# ch1.net
KiCad netlist of a schematic drawn in EAGLE
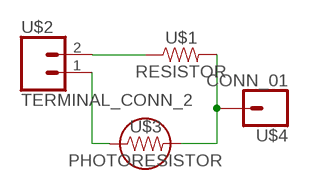
[diagram p0: schematic, sheet 1]

(export (version "E")
  (design (tool "Eeschema 10.0.6"))
  (components
    (comp (ref "U$1")
      (value "RESISTOR")
      (footprint "eagle-import:RESISTOR")
      (libsource (lib "eagle-import") (part "RESISTOR"))
    )
    (comp (ref "U$2")
      (value "TERMINAL_CONN_2")
      (footprint "eagle-import:TERMINAL_CONN_2")
      (libsource (lib "eagle-import") (part "TERMINAL_CONN_2"))
    )
    (comp (ref "U$3")
      (value "PHOTORESISTOR")
      (footprint "eagle-import:PHOTORESISTOR")
      (libsource (lib "eagle-import") (part "PHOTORESISTOR"))
    )
    (comp (ref "U$4")
      (value "CONN_01")
      (footprint "eagle-import:1X01")
      (libsource (lib "eagle-import") (part "CONN_01"))
    )
  )
  (nets
    (net (code "1") (name "Net-(U$1-Pad1)") (class "Default")
      (node (ref "U$1") (pin "1") (pinfunction "1_1") (pintype "passive"))
      (node (ref "U$2") (pin "2") (pinfunction "2_2") (pintype "passive"))
    )
    (net (code "2") (name "Net-(U$3-1)") (class "Default")
      (node (ref "U$2") (pin "1") (pinfunction "1_1") (pintype "passive"))
      (node (ref "U$3") (pin "P$1") (pinfunction "1_P$1") (pintype "passive"))
    )
    (net (code "3") (name "Net-(U$3-2)") (class "Default")
      (node (ref "U$1") (pin "2") (pinfunction "2_2") (pintype "passive"))
      (node (ref "U$3") (pin "P$2") (pinfunction "2_P$2") (pintype "passive"))
      (node (ref "U$4") (pin "1") (pinfunction "1_1") (pintype "passive"))
    )
  )
)
